# SchemaSplit.net
KiCad netlist of a schematic drawn in Altium Designer
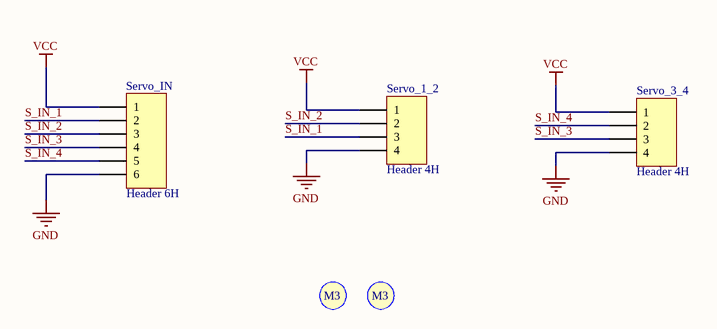
[diagram p0: SchemaSplit.SchDoc]

(export (version "E")
  (design (tool "Eeschema 10.0.6"))
  (components
    (comp (ref "S1")
      (value "Screw M3")
      (footprint "Screw M3")
      (libsource (lib "Robot_2019") (part "Screw M3"))
    )
    (comp (ref "S2")
      (value "Screw M3")
      (footprint "Screw M3")
      (libsource (lib "Robot_2019") (part "Screw M3"))
    )
    (comp (ref "Servo_1_2")
      (value "Header 4H")
      (footprint "S4B-XH-A")
      (description "Header, 4-Pin, Right Angle")
      (fields (field (name "PUBLISHER") "Altium Limited"))
      (libsource (lib "Miscellaneous Connectors") (part "Header 4H"))
    )
    (comp (ref "Servo_3_4")
      (value "Header 4H")
      (footprint "S4B-XH-A")
      (description "Header, 4-Pin, Right Angle")
      (fields (field (name "PUBLISHER") "Altium Limited"))
      (libsource (lib "Miscellaneous Connectors") (part "Header 4H"))
    )
    (comp (ref "Servo_IN")
      (value "Header 6H")
      (footprint "S6B-XH-A")
      (description "Header, 6-Pin, Right Angle")
      (fields (field (name "PUBLISHER") "Altium Limited"))
      (libsource (lib "Miscellaneous Connectors") (part "Header 6H"))
    )
  )
  (nets
    (net (code "1") (name "/S_IN_1") (class "Default")
      (node (ref "Servo_1_2") (pin "3") (pinfunction "3_3") (pintype "passive"))
      (node (ref "Servo_IN") (pin "2") (pinfunction "2_2") (pintype "passive"))
    )
    (net (code "2") (name "/S_IN_2") (class "Default")
      (node (ref "Servo_1_2") (pin "2") (pinfunction "2_2") (pintype "passive"))
      (node (ref "Servo_IN") (pin "3") (pinfunction "3_3") (pintype "passive"))
    )
    (net (code "3") (name "/S_IN_3") (class "Default")
      (node (ref "Servo_3_4") (pin "3") (pinfunction "3_3") (pintype "passive"))
      (node (ref "Servo_IN") (pin "4") (pinfunction "4_4") (pintype "passive"))
    )
    (net (code "4") (name "/S_IN_4") (class "Default")
      (node (ref "Servo_3_4") (pin "2") (pinfunction "2_2") (pintype "passive"))
      (node (ref "Servo_IN") (pin "5") (pinfunction "5_5") (pintype "passive"))
    )
    (net (code "5") (name "GND") (class "Default")
      (node (ref "Servo_1_2") (pin "4") (pinfunction "4_4") (pintype "passive"))
      (node (ref "Servo_3_4") (pin "4") (pinfunction "4_4") (pintype "passive"))
      (node (ref "Servo_IN") (pin "6") (pinfunction "6_6") (pintype "passive"))
    )
    (net (code "6") (name "VCC") (class "Default")
      (node (ref "Servo_1_2") (pin "1") (pinfunction "1_1") (pintype "passive"))
      (node (ref "Servo_3_4") (pin "1") (pinfunction "1_1") (pintype "passive"))
      (node (ref "Servo_IN") (pin "1") (pinfunction "1_1") (pintype "passive"))
    )
  )
)
